# 03-Front_Panel_SFP_1.net
KiCad netlist of a schematic drawn in Altium Designer
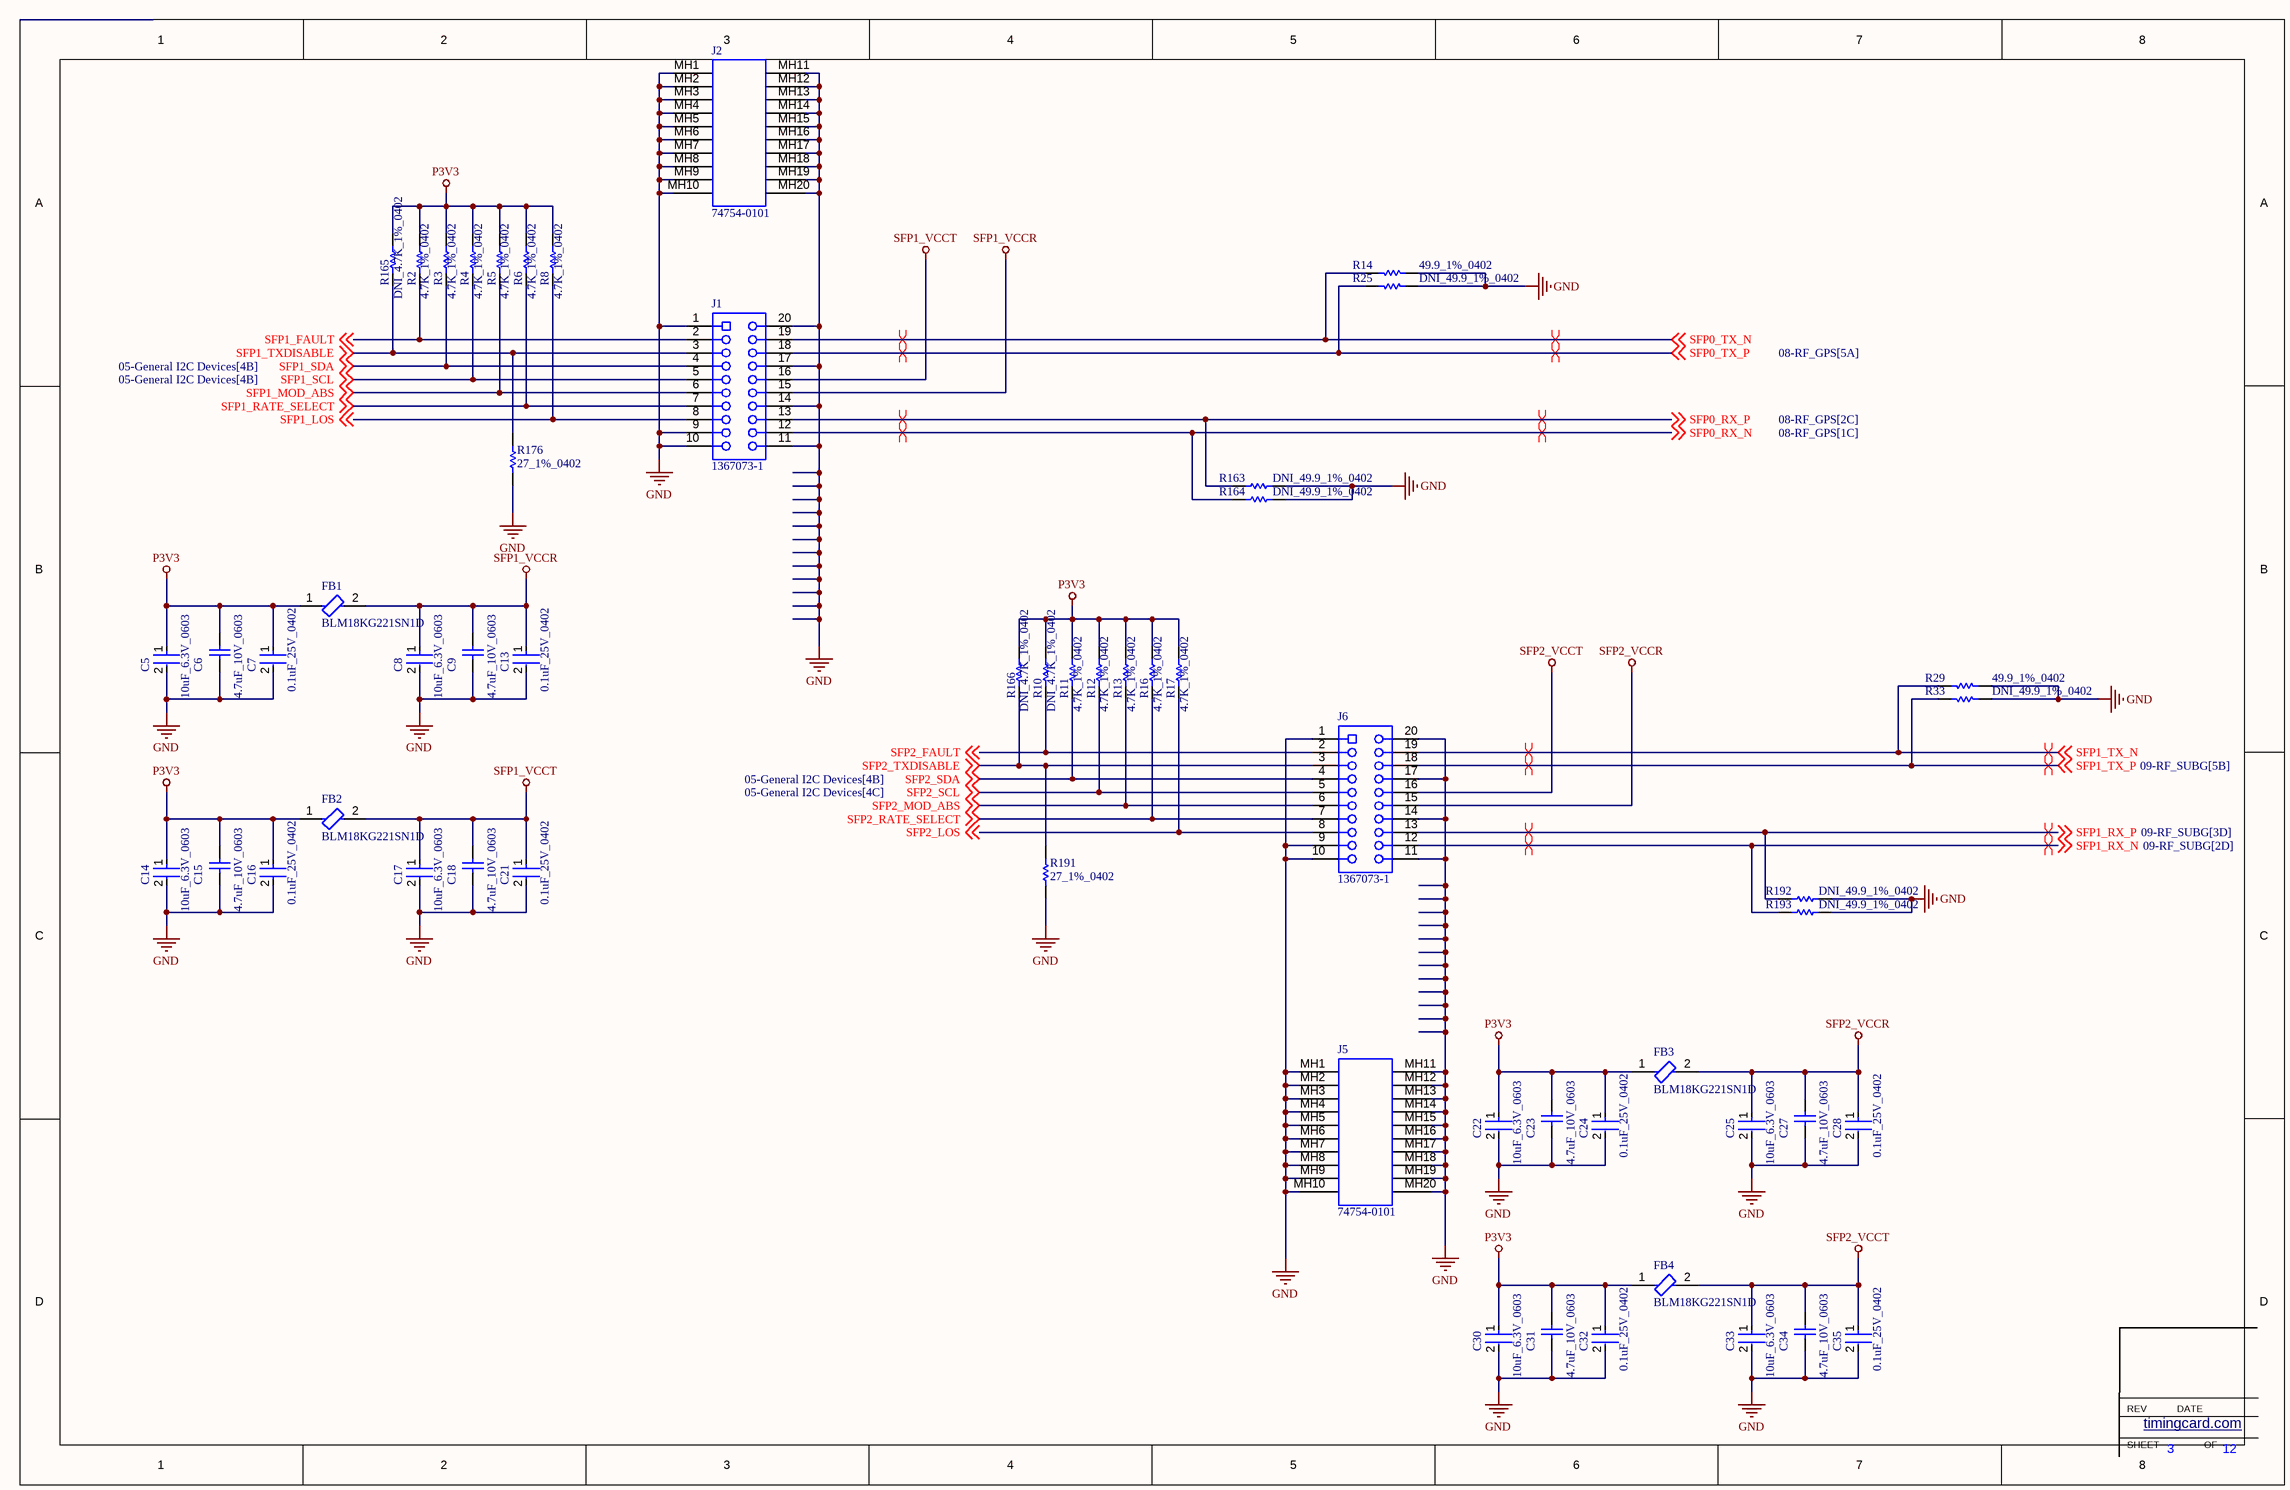
[diagram p0: 03-Front Panel SFP_1.SchDoc]

(export (version "E")
  (design (tool "Eeschema 10.0.6"))
  (components
    (comp (ref "C5")
      (value "10uF_6.3V_0603")
      (footprint "FP-C0603C106M9PACTU-MFG")
      (description "CAP CER 10UF 6.3V X5R 0603")
      (fields
        (field (name "MANUFACTURER PART NUMBER") "C0603C106M9PACTU")
        (field (name "MANUFACTURER") "Kemet")
      )
      (libsource (lib "Altium Content Vault") (part "b4654b650e69147ec39a6b967a45e02"))
    )
    (comp (ref "C6")
      (value "4.7uF_10V_0603")
      (footprint "CAPC1608X87X35NL15T15")
      (fields (field (name "PART NUMBER") "C0603C475K8PACTU") (field (name "MANUFACTURER") "Kemet"))
      (libsource (lib "Altium Content Vault") (part "CAP"))
    )
    (comp (ref "C7")
      (value "0.1uF_25V_0402")
      (footprint "FP-0402-L_1_0_1-W_0_5_0_1-IPC_C")
      (description "General Purpose Ceramic Capacitor, 0402, 100nF, 10%, X7R, 15%, 25V")
      (fields (field (name "VOLTAGE") "25V") (field (name "TOLERANCE") "10%"))
      (libsource (lib "Altium Content Vault") (part "b4654b650e69147ec39a6b967a45e02"))
    )
    (comp (ref "C8")
      (value "10uF_6.3V_0603")
      (footprint "FP-C0603C106M9PACTU-MFG")
      (description "CAP CER 10UF 6.3V X5R 0603")
      (fields
        (field (name "MANUFACTURER PART NUMBER") "C0603C106M9PACTU")
        (field (name "MANUFACTURER") "Kemet")
      )
      (libsource (lib "Altium Content Vault") (part "b4654b650e69147ec39a6b967a45e02"))
    )
    (comp (ref "C9")
      (value "4.7uF_10V_0603")
      (footprint "CAPC1608X87X35NL15T15")
      (fields (field (name "PART NUMBER") "C0603C475K8PACTU") (field (name "MANUFACTURER") "Kemet"))
      (libsource (lib "Altium Content Vault") (part "CAP"))
    )
    (comp (ref "C13")
      (value "0.1uF_25V_0402")
      (footprint "FP-0402-L_1_0_1-W_0_5_0_1-IPC_C")
      (description "General Purpose Ceramic Capacitor, 0402, 100nF, 10%, X7R, 15%, 25V")
      (fields (field (name "VOLTAGE") "25V") (field (name "TOLERANCE") "10%"))
      (libsource (lib "Altium Content Vault") (part "b4654b650e69147ec39a6b967a45e02"))
    )
    (comp (ref "C14")
      (value "10uF_6.3V_0603")
      (footprint "FP-C0603C106M9PACTU-MFG")
      (description "CAP CER 10UF 6.3V X5R 0603")
      (fields
        (field (name "MANUFACTURER PART NUMBER") "C0603C106M9PACTU")
        (field (name "MANUFACTURER") "Kemet")
      )
      (libsource (lib "Altium Content Vault") (part "b4654b650e69147ec39a6b967a45e02"))
    )
    (comp (ref "C15")
      (value "4.7uF_10V_0603")
      (footprint "CAPC1608X87X35NL15T15")
      (fields (field (name "PART NUMBER") "C0603C475K8PACTU") (field (name "MANUFACTURER") "Kemet"))
      (libsource (lib "Altium Content Vault") (part "CAP"))
    )
    (comp (ref "C16")
      (value "0.1uF_25V_0402")
      (footprint "FP-0402-L_1_0_1-W_0_5_0_1-IPC_C")
      (description "General Purpose Ceramic Capacitor, 0402, 100nF, 10%, X7R, 15%, 25V")
      (fields (field (name "VOLTAGE") "25V") (field (name "TOLERANCE") "10%"))
      (libsource (lib "Altium Content Vault") (part "b4654b650e69147ec39a6b967a45e02"))
    )
    (comp (ref "C17")
      (value "10uF_6.3V_0603")
      (footprint "FP-C0603C106M9PACTU-MFG")
      (description "CAP CER 10UF 6.3V X5R 0603")
      (fields
        (field (name "MANUFACTURER PART NUMBER") "C0603C106M9PACTU")
        (field (name "MANUFACTURER") "Kemet")
      )
      (libsource (lib "Altium Content Vault") (part "b4654b650e69147ec39a6b967a45e02"))
    )
    (comp (ref "C18")
      (value "4.7uF_10V_0603")
      (footprint "CAPC1608X87X35NL15T15")
      (fields (field (name "PART NUMBER") "C0603C475K8PACTU") (field (name "MANUFACTURER") "Kemet"))
      (libsource (lib "Altium Content Vault") (part "CAP"))
    )
    (comp (ref "C21")
      (value "0.1uF_25V_0402")
      (footprint "FP-0402-L_1_0_1-W_0_5_0_1-IPC_C")
      (description "General Purpose Ceramic Capacitor, 0402, 100nF, 10%, X7R, 15%, 25V")
      (fields (field (name "VOLTAGE") "25V") (field (name "TOLERANCE") "10%"))
      (libsource (lib "Altium Content Vault") (part "b4654b650e69147ec39a6b967a45e02"))
    )
    (comp (ref "C22")
      (value "10uF_6.3V_0603")
      (footprint "FP-C0603C106M9PACTU-MFG")
      (description "CAP CER 10UF 6.3V X5R 0603")
      (fields
        (field (name "MANUFACTURER PART NUMBER") "C0603C106M9PACTU")
        (field (name "MANUFACTURER") "Kemet")
      )
      (libsource (lib "Altium Content Vault") (part "b4654b650e69147ec39a6b967a45e02"))
    )
    (comp (ref "C23")
      (value "4.7uF_10V_0603")
      (footprint "CAPC1608X87X35NL15T15")
      (fields (field (name "PART NUMBER") "C0603C475K8PACTU") (field (name "MANUFACTURER") "Kemet"))
      (libsource (lib "Altium Content Vault") (part "CAP"))
    )
    (comp (ref "C24")
      (value "0.1uF_25V_0402")
      (footprint "FP-0402-L_1_0_1-W_0_5_0_1-IPC_C")
      (description "General Purpose Ceramic Capacitor, 0402, 100nF, 10%, X7R, 15%, 25V")
      (fields (field (name "VOLTAGE") "25V") (field (name "TOLERANCE") "10%"))
      (libsource (lib "Altium Content Vault") (part "b4654b650e69147ec39a6b967a45e02"))
    )
    (comp (ref "C25")
      (value "10uF_6.3V_0603")
      (footprint "FP-C0603C106M9PACTU-MFG")
      (description "CAP CER 10UF 6.3V X5R 0603")
      (fields
        (field (name "MANUFACTURER PART NUMBER") "C0603C106M9PACTU")
        (field (name "MANUFACTURER") "Kemet")
      )
      (libsource (lib "Altium Content Vault") (part "b4654b650e69147ec39a6b967a45e02"))
    )
    (comp (ref "C27")
      (value "4.7uF_10V_0603")
      (footprint "CAPC1608X87X35NL15T15")
      (fields (field (name "PART NUMBER") "C0603C475K8PACTU") (field (name "MANUFACTURER") "Kemet"))
      (libsource (lib "Altium Content Vault") (part "CAP"))
    )
    (comp (ref "C28")
      (value "0.1uF_25V_0402")
      (footprint "FP-0402-L_1_0_1-W_0_5_0_1-IPC_C")
      (description "General Purpose Ceramic Capacitor, 0402, 100nF, 10%, X7R, 15%, 25V")
      (fields (field (name "VOLTAGE") "25V") (field (name "TOLERANCE") "10%"))
      (libsource (lib "Altium Content Vault") (part "b4654b650e69147ec39a6b967a45e02"))
    )
    (comp (ref "C30")
      (value "10uF_6.3V_0603")
      (footprint "FP-C0603C106M9PACTU-MFG")
      (description "CAP CER 10UF 6.3V X5R 0603")
      (fields
        (field (name "MANUFACTURER PART NUMBER") "C0603C106M9PACTU")
        (field (name "MANUFACTURER") "Kemet")
      )
      (libsource (lib "Altium Content Vault") (part "b4654b650e69147ec39a6b967a45e02"))
    )
    (comp (ref "C31")
      (value "4.7uF_10V_0603")
      (footprint "CAPC1608X87X35NL15T15")
      (fields (field (name "PART NUMBER") "C0603C475K8PACTU") (field (name "MANUFACTURER") "Kemet"))
      (libsource (lib "Altium Content Vault") (part "CAP"))
    )
    (comp (ref "C32")
      (value "0.1uF_25V_0402")
      (footprint "FP-0402-L_1_0_1-W_0_5_0_1-IPC_C")
      (description "General Purpose Ceramic Capacitor, 0402, 100nF, 10%, X7R, 15%, 25V")
      (fields (field (name "VOLTAGE") "25V") (field (name "TOLERANCE") "10%"))
      (libsource (lib "Altium Content Vault") (part "b4654b650e69147ec39a6b967a45e02"))
    )
    (comp (ref "C33")
      (value "10uF_6.3V_0603")
      (footprint "FP-C0603C106M9PACTU-MFG")
      (description "CAP CER 10UF 6.3V X5R 0603")
      (fields
        (field (name "MANUFACTURER PART NUMBER") "C0603C106M9PACTU")
        (field (name "MANUFACTURER") "Kemet")
      )
      (libsource (lib "Altium Content Vault") (part "b4654b650e69147ec39a6b967a45e02"))
    )
    (comp (ref "C34")
      (value "4.7uF_10V_0603")
      (footprint "CAPC1608X87X35NL15T15")
      (fields (field (name "PART NUMBER") "C0603C475K8PACTU") (field (name "MANUFACTURER") "Kemet"))
      (libsource (lib "Altium Content Vault") (part "CAP"))
    )
    (comp (ref "C35")
      (value "0.1uF_25V_0402")
      (footprint "FP-0402-L_1_0_1-W_0_5_0_1-IPC_C")
      (description "General Purpose Ceramic Capacitor, 0402, 100nF, 10%, X7R, 15%, 25V")
      (fields (field (name "VOLTAGE") "25V") (field (name "TOLERANCE") "10%"))
      (libsource (lib "Altium Content Vault") (part "b4654b650e69147ec39a6b967a45e02"))
    )
    (comp (ref "FB1")
      (value "BLM18KG221SN1D")
      (footprint "FP-BLM18-0_15-t0_8-IPC_B")
      (description "Chip Ferrite Bead, 0603, 220Ω @ 100MHz, 0.05Ω, 25%, 2.2A")
      (fields (field (name "TOLERANCE") "25%"))
      (libsource (lib "Altium Content Vault") (part "5f30dd21d616792df468990f7003faa"))
    )
    (comp (ref "FB2")
      (value "BLM18KG221SN1D")
      (footprint "FP-BLM18-0_15-t0_8-IPC_B")
      (description "Chip Ferrite Bead, 0603, 220Ω @ 100MHz, 0.05Ω, 25%, 2.2A")
      (fields (field (name "TOLERANCE") "25%"))
      (libsource (lib "Altium Content Vault") (part "5f30dd21d616792df468990f7003faa"))
    )
    (comp (ref "FB3")
      (value "BLM18KG221SN1D")
      (footprint "FP-BLM18-0_15-t0_8-IPC_B")
      (description "Chip Ferrite Bead, 0603, 220Ω @ 100MHz, 0.05Ω, 25%, 2.2A")
      (fields (field (name "TOLERANCE") "25%"))
      (libsource (lib "Altium Content Vault") (part "5f30dd21d616792df468990f7003faa"))
    )
    (comp (ref "FB4")
      (value "BLM18KG221SN1D")
      (footprint "FP-BLM18-0_15-t0_8-IPC_B")
      (description "Chip Ferrite Bead, 0603, 220Ω @ 100MHz, 0.05Ω, 25%, 2.2A")
      (fields (field (name "TOLERANCE") "25%"))
      (libsource (lib "Altium Content Vault") (part "5f30dd21d616792df468990f7003faa"))
    )
    (comp (ref "J1")
      (value "1367073-1")
      (footprint "TECO-1367073-1_V")
      (fields (field (name "MANUFACTURER") "TE Connectivity"))
      (libsource (lib "Altium Content Vault") (part "CN-2P-F-R20_B"))
    )
    (comp (ref "J2")
      (value "74754-0101")
      (footprint "MOLX-74754-0101_V")
      (description "SFP+ Cage, Single Port, Height 10.85 mm, Tail Height 3.05 mm, -40 to 85 degC, RoHS, Tray")
      (libsource (lib "Altium Content Vault") (part "MOLX-74754-0101"))
    )
    (comp (ref "J5")
      (value "74754-0101")
      (footprint "MOLX-74754-0101_V")
      (description "SFP+ Cage, Single Port, Height 10.85 mm, Tail Height 3.05 mm, -40 to 85 degC, RoHS, Tray")
      (libsource (lib "Altium Content Vault") (part "MOLX-74754-0101"))
    )
    (comp (ref "J6")
      (value "1367073-1")
      (footprint "TECO-1367073-1_V")
      (fields (field (name "MANUFACTURER") "TE Connectivity"))
      (libsource (lib "Altium Content Vault") (part "CN-2P-F-R20_B"))
    )
    (comp (ref "R2")
      (value "4.7K_1%_0402")
      (footprint "RESC1005X40X25NL10T10")
      (fields (field (name "MANUFACTURER") "Bourns") (field (name "PART NUMBER") "CR0402-FX-4701GLF"))
      (libsource (lib "Altium Content Vault") (part "RES"))
    )
    (comp (ref "R3")
      (value "4.7K_1%_0402")
      (footprint "RESC1005X40X25NL10T10")
      (fields (field (name "MANUFACTURER") "Bourns") (field (name "PART NUMBER") "CR0402-FX-4701GLF"))
      (libsource (lib "Altium Content Vault") (part "RES"))
    )
    (comp (ref "R4")
      (value "4.7K_1%_0402")
      (footprint "RESC1005X40X25NL10T10")
      (fields (field (name "MANUFACTURER") "Bourns") (field (name "PART NUMBER") "CR0402-FX-4701GLF"))
      (libsource (lib "Altium Content Vault") (part "RES"))
    )
    (comp (ref "R5")
      (value "4.7K_1%_0402")
      (footprint "RESC1005X40X25NL10T10")
      (fields (field (name "MANUFACTURER") "Bourns") (field (name "PART NUMBER") "CR0402-FX-4701GLF"))
      (libsource (lib "Altium Content Vault") (part "RES"))
    )
    (comp (ref "R6")
      (value "4.7K_1%_0402")
      (footprint "RESC1005X40X25NL10T10")
      (fields (field (name "MANUFACTURER") "Bourns") (field (name "PART NUMBER") "CR0402-FX-4701GLF"))
      (libsource (lib "Altium Content Vault") (part "RES"))
    )
    (comp (ref "R8")
      (value "4.7K_1%_0402")
      (footprint "RESC1005X40X25NL10T10")
      (fields (field (name "MANUFACTURER") "Bourns") (field (name "PART NUMBER") "CR0402-FX-4701GLF"))
      (libsource (lib "Altium Content Vault") (part "RES"))
    )
    (comp (ref "R10")
      (value "DNI_4.7K_1%_0402")
      (footprint "RESC1005X40X25NL10T10")
      (fields (field (name "MANUFACTURER") "Bourns") (field (name "PART NUMBER") "CR0402-FX-4701GLF"))
      (libsource (lib "Altium Content Vault") (part "RES"))
    )
    (comp (ref "R11")
      (value "4.7K_1%_0402")
      (footprint "RESC1005X40X25NL10T10")
      (fields (field (name "MANUFACTURER") "Bourns") (field (name "PART NUMBER") "CR0402-FX-4701GLF"))
      (libsource (lib "Altium Content Vault") (part "RES"))
    )
    (comp (ref "R12")
      (value "4.7K_1%_0402")
      (footprint "RESC1005X40X25NL10T10")
      (fields (field (name "MANUFACTURER") "Bourns") (field (name "PART NUMBER") "CR0402-FX-4701GLF"))
      (libsource (lib "Altium Content Vault") (part "RES"))
    )
    (comp (ref "R13")
      (value "4.7K_1%_0402")
      (footprint "RESC1005X40X25NL10T10")
      (fields (field (name "MANUFACTURER") "Bourns") (field (name "PART NUMBER") "CR0402-FX-4701GLF"))
      (libsource (lib "Altium Content Vault") (part "RES"))
    )
    (comp (ref "R14")
      (value "49.9_1%_0402")
      (footprint "RESC1005X40X25NL10T10")
      (fields (field (name "PART NUMBER") "RK73H1ETTP49R9F") (field (name "MANUFACTURER") "KOA Speer"))
      (libsource (lib "Altium Content Vault") (part "RES"))
    )
    (comp (ref "R16")
      (value "4.7K_1%_0402")
      (footprint "RESC1005X40X25NL10T10")
      (fields (field (name "MANUFACTURER") "Bourns") (field (name "PART NUMBER") "CR0402-FX-4701GLF"))
      (libsource (lib "Altium Content Vault") (part "RES"))
    )
    (comp (ref "R17")
      (value "4.7K_1%_0402")
      (footprint "RESC1005X40X25NL10T10")
      (fields (field (name "MANUFACTURER") "Bourns") (field (name "PART NUMBER") "CR0402-FX-4701GLF"))
      (libsource (lib "Altium Content Vault") (part "RES"))
    )
    (comp (ref "R25")
      (value "DNI_49.9_1%_0402")
      (footprint "RESC1005X40X25NL10T10")
      (fields (field (name "PART NUMBER") "RK73H1ETTP49R9F") (field (name "MANUFACTURER") "KOA Speer"))
      (libsource (lib "Altium Content Vault") (part "RES"))
    )
    (comp (ref "R29")
      (value "49.9_1%_0402")
      (footprint "RESC1005X40X25NL10T10")
      (fields (field (name "PART NUMBER") "RK73H1ETTP49R9F") (field (name "MANUFACTURER") "KOA Speer"))
      (libsource (lib "Altium Content Vault") (part "RES"))
    )
    (comp (ref "R33")
      (value "DNI_49.9_1%_0402")
      (footprint "RESC1005X40X25NL10T10")
      (fields (field (name "PART NUMBER") "RK73H1ETTP49R9F") (field (name "MANUFACTURER") "KOA Speer"))
      (libsource (lib "Altium Content Vault") (part "RES"))
    )
    (comp (ref "R163")
      (value "DNI_49.9_1%_0402")
      (footprint "RESC1005X40X25NL10T10")
      (fields (field (name "PART NUMBER") "RK73H1ETTP49R9F") (field (name "MANUFACTURER") "KOA Speer"))
      (libsource (lib "Altium Content Vault") (part "RES"))
    )
    (comp (ref "R164")
      (value "DNI_49.9_1%_0402")
      (footprint "RESC1005X40X25NL10T10")
      (fields (field (name "PART NUMBER") "RK73H1ETTP49R9F") (field (name "MANUFACTURER") "KOA Speer"))
      (libsource (lib "Altium Content Vault") (part "RES"))
    )
    (comp (ref "R165")
      (value "DNI_4.7K_1%_0402")
      (footprint "RESC1005X40X25NL10T10")
      (fields (field (name "MANUFACTURER") "Bourns") (field (name "PART NUMBER") "CR0402-FX-4701GLF"))
      (libsource (lib "Altium Content Vault") (part "RES"))
    )
    (comp (ref "R166")
      (value "DNI_4.7K_1%_0402")
      (footprint "RESC1005X40X25NL10T10")
      (fields (field (name "MANUFACTURER") "Bourns") (field (name "PART NUMBER") "CR0402-FX-4701GLF"))
      (libsource (lib "Altium Content Vault") (part "RES"))
    )
    (comp (ref "R176")
      (value "27_1%_0402")
      (footprint "RESC1005X40X25NL05T05")
      (fields (field (name "PART NUMBER") "CRCW040227R0FKED") (field (name "MANUFACTURER") "Vishay Dale"))
      (libsource (lib "Altium Content Vault") (part "RES"))
    )
    (comp (ref "R191")
      (value "27_1%_0402")
      (footprint "RESC1005X40X25NL05T05")
      (fields (field (name "PART NUMBER") "CRCW040227R0FKED") (field (name "MANUFACTURER") "Vishay Dale"))
      (libsource (lib "Altium Content Vault") (part "RES"))
    )
    (comp (ref "R192")
      (value "DNI_49.9_1%_0402")
      (footprint "RESC1005X40X25NL10T10")
      (fields (field (name "PART NUMBER") "RK73H1ETTP49R9F") (field (name "MANUFACTURER") "KOA Speer"))
      (libsource (lib "Altium Content Vault") (part "RES"))
    )
    (comp (ref "R193")
      (value "DNI_49.9_1%_0402")
      (footprint "RESC1005X40X25NL10T10")
      (fields (field (name "PART NUMBER") "RK73H1ETTP49R9F") (field (name "MANUFACTURER") "KOA Speer"))
      (libsource (lib "Altium Content Vault") (part "RES"))
    )
  )
  (nets
    (net (code "1") (name "GND") (class "Default")
      (node (ref "C13") (pin "2") (pinfunction "2_2") (pintype "passive"))
      (node (ref "C14") (pin "2") (pinfunction "2_2") (pintype "passive"))
      (node (ref "C15") (pin "1") (pinfunction "1_1") (pintype "passive"))
      (node (ref "C16") (pin "2") (pinfunction "2_2") (pintype "passive"))
      (node (ref "C17") (pin "2") (pinfunction "2_2") (pintype "passive"))
      (node (ref "C18") (pin "1") (pinfunction "1_1") (pintype "passive"))
      (node (ref "C21") (pin "2") (pinfunction "2_2") (pintype "passive"))
      (node (ref "C22") (pin "2") (pinfunction "2_2") (pintype "passive"))
      (node (ref "C23") (pin "1") (pinfunction "1_1") (pintype "passive"))
      (node (ref "C24") (pin "2") (pinfunction "2_2") (pintype "passive"))
      (node (ref "C25") (pin "2") (pinfunction "2_2") (pintype "passive"))
      (node (ref "C27") (pin "1") (pinfunction "1_1") (pintype "passive"))
      (node (ref "C28") (pin "2") (pinfunction "2_2") (pintype "passive"))
      (node (ref "C30") (pin "2") (pinfunction "2_2") (pintype "passive"))
      (node (ref "C31") (pin "1") (pinfunction "1_1") (pintype "passive"))
      (node (ref "C32") (pin "2") (pinfunction "2_2") (pintype "passive"))
      (node (ref "C33") (pin "2") (pinfunction "2_2") (pintype "passive"))
      (node (ref "C34") (pin "1") (pinfunction "1_1") (pintype "passive"))
      (node (ref "C35") (pin "2") (pinfunction "2_2") (pintype "passive"))
      (node (ref "C5") (pin "2") (pinfunction "2_2") (pintype "passive"))
      (node (ref "C6") (pin "1") (pinfunction "1_1") (pintype "passive"))
      (node (ref "C7") (pin "2") (pinfunction "2_2") (pintype "passive"))
      (node (ref "C8") (pin "2") (pinfunction "2_2") (pintype "passive"))
      (node (ref "C9") (pin "1") (pinfunction "1_1") (pintype "passive"))
      (node (ref "J1") (pin "1") (pinfunction "1_1") (pintype "passive"))
      (node (ref "J1") (pin "10") (pinfunction "10_10") (pintype "passive"))
      (node (ref "J1") (pin "11") (pinfunction "11_11") (pintype "passive"))
      (node (ref "J1") (pin "14") (pinfunction "14_14") (pintype "passive"))
      (node (ref "J1") (pin "17") (pinfunction "17_17") (pintype "passive"))
      (node (ref "J1") (pin "20") (pinfunction "20_20") (pintype "passive"))
      (node (ref "J1") (pin "9") (pinfunction "9_9") (pintype "passive"))
      (node (ref "J2") (pin "MH1") (pinfunction "MH1_MH1") (pintype "passive"))
      (node (ref "J2") (pin "MH10") (pinfunction "MH10_MH10") (pintype "passive"))
      (node (ref "J2") (pin "MH11") (pinfunction "MH11_MH11") (pintype "passive"))
      (node (ref "J2") (pin "MH12") (pinfunction "MH12_MH12") (pintype "passive"))
      (node (ref "J2") (pin "MH13") (pinfunction "MH13_MH13") (pintype "passive"))
      (node (ref "J2") (pin "MH14") (pinfunction "MH14_MH14") (pintype "passive"))
      (node (ref "J2") (pin "MH15") (pinfunction "MH15_MH15") (pintype "passive"))
      (node (ref "J2") (pin "MH16") (pinfunction "MH16_MH16") (pintype "passive"))
      (node (ref "J2") (pin "MH17") (pinfunction "MH17_MH17") (pintype "passive"))
      (node (ref "J2") (pin "MH18") (pinfunction "MH18_MH18") (pintype "passive"))
      (node (ref "J2") (pin "MH19") (pinfunction "MH19_MH19") (pintype "passive"))
      (node (ref "J2") (pin "MH2") (pinfunction "MH2_MH2") (pintype "passive"))
      (node (ref "J2") (pin "MH20") (pinfunction "MH20_MH20") (pintype "passive"))
      (node (ref "J2") (pin "MH3") (pinfunction "MH3_MH3") (pintype "passive"))
      (node (ref "J2") (pin "MH4") (pinfunction "MH4_MH4") (pintype "passive"))
      (node (ref "J2") (pin "MH5") (pinfunction "MH5_MH5") (pintype "passive"))
      (node (ref "J2") (pin "MH6") (pinfunction "MH6_MH6") (pintype "passive"))
      (node (ref "J2") (pin "MH7") (pinfunction "MH7_MH7") (pintype "passive"))
      (node (ref "J2") (pin "MH8") (pinfunction "MH8_MH8") (pintype "passive"))
      (node (ref "J2") (pin "MH9") (pinfunction "MH9_MH9") (pintype "passive"))
      (node (ref "J5") (pin "MH1") (pinfunction "MH1_MH1") (pintype "passive"))
      (node (ref "J5") (pin "MH10") (pinfunction "MH10_MH10") (pintype "passive"))
      (node (ref "J5") (pin "MH11") (pinfunction "MH11_MH11") (pintype "passive"))
      (node (ref "J5") (pin "MH12") (pinfunction "MH12_MH12") (pintype "passive"))
      (node (ref "J5") (pin "MH13") (pinfunction "MH13_MH13") (pintype "passive"))
      (node (ref "J5") (pin "MH14") (pinfunction "MH14_MH14") (pintype "passive"))
      (node (ref "J5") (pin "MH15") (pinfunction "MH15_MH15") (pintype "passive"))
      (node (ref "J5") (pin "MH16") (pinfunction "MH16_MH16") (pintype "passive"))
      (node (ref "J5") (pin "MH17") (pinfunction "MH17_MH17") (pintype "passive"))
      (node (ref "J5") (pin "MH18") (pinfunction "MH18_MH18") (pintype "passive"))
      (node (ref "J5") (pin "MH19") (pinfunction "MH19_MH19") (pintype "passive"))
      (node (ref "J5") (pin "MH2") (pinfunction "MH2_MH2") (pintype "passive"))
      (node (ref "J5") (pin "MH20") (pinfunction "MH20_MH20") (pintype "passive"))
      (node (ref "J5") (pin "MH3") (pinfunction "MH3_MH3") (pintype "passive"))
      (node (ref "J5") (pin "MH4") (pinfunction "MH4_MH4") (pintype "passive"))
      (node (ref "J5") (pin "MH5") (pinfunction "MH5_MH5") (pintype "passive"))
      (node (ref "J5") (pin "MH6") (pinfunction "MH6_MH6") (pintype "passive"))
      (node (ref "J5") (pin "MH7") (pinfunction "MH7_MH7") (pintype "passive"))
      (node (ref "J5") (pin "MH8") (pinfunction "MH8_MH8") (pintype "passive"))
      (node (ref "J5") (pin "MH9") (pinfunction "MH9_MH9") (pintype "passive"))
      (node (ref "J6") (pin "1") (pinfunction "1_1") (pintype "passive"))
      (node (ref "J6") (pin "10") (pinfunction "10_10") (pintype "passive"))
      (node (ref "J6") (pin "11") (pinfunction "11_11") (pintype "passive"))
      (node (ref "J6") (pin "14") (pinfunction "14_14") (pintype "passive"))
      (node (ref "J6") (pin "17") (pinfunction "17_17") (pintype "passive"))
      (node (ref "J6") (pin "20") (pinfunction "20_20") (pintype "passive"))
      (node (ref "J6") (pin "9") (pinfunction "9_9") (pintype "passive"))
      (node (ref "R14") (pin "2") (pinfunction "2_2") (pintype "passive"))
      (node (ref "R163") (pin "2") (pinfunction "2_2") (pintype "passive"))
      (node (ref "R164") (pin "2") (pinfunction "2_2") (pintype "passive"))
      (node (ref "R176") (pin "1") (pinfunction "1_1") (pintype "passive"))
      (node (ref "R191") (pin "1") (pinfunction "1_1") (pintype "passive"))
      (node (ref "R192") (pin "2") (pinfunction "2_2") (pintype "passive"))
      (node (ref "R193") (pin "2") (pinfunction "2_2") (pintype "passive"))
      (node (ref "R25") (pin "2") (pinfunction "2_2") (pintype "passive"))
      (node (ref "R29") (pin "2") (pinfunction "2_2") (pintype "passive"))
      (node (ref "R33") (pin "2") (pinfunction "2_2") (pintype "passive"))
    )
    (net (code "2") (name "P3V3") (class "Default")
      (node (ref "C14") (pin "1") (pinfunction "1_1") (pintype "passive"))
      (node (ref "C15") (pin "2") (pinfunction "2_2") (pintype "passive"))
      (node (ref "C16") (pin "1") (pinfunction "1_1") (pintype "passive"))
      (node (ref "C22") (pin "1") (pinfunction "1_1") (pintype "passive"))
      (node (ref "C23") (pin "2") (pinfunction "2_2") (pintype "passive"))
      (node (ref "C24") (pin "1") (pinfunction "1_1") (pintype "passive"))
      (node (ref "C30") (pin "1") (pinfunction "1_1") (pintype "passive"))
      (node (ref "C31") (pin "2") (pinfunction "2_2") (pintype "passive"))
      (node (ref "C32") (pin "1") (pinfunction "1_1") (pintype "passive"))
      (node (ref "C5") (pin "1") (pinfunction "1_1") (pintype "passive"))
      (node (ref "C6") (pin "2") (pinfunction "2_2") (pintype "passive"))
      (node (ref "C7") (pin "1") (pinfunction "1_1") (pintype "passive"))
      (node (ref "FB1") (pin "1") (pinfunction "1_1") (pintype "passive"))
      (node (ref "FB2") (pin "1") (pinfunction "1_1") (pintype "passive"))
      (node (ref "FB3") (pin "1") (pinfunction "1_1") (pintype "passive"))
      (node (ref "FB4") (pin "1") (pinfunction "1_1") (pintype "passive"))
      (node (ref "R10") (pin "1") (pinfunction "1_1") (pintype "passive"))
      (node (ref "R11") (pin "1") (pinfunction "1_1") (pintype "passive"))
      (node (ref "R12") (pin "1") (pinfunction "1_1") (pintype "passive"))
      (node (ref "R13") (pin "1") (pinfunction "1_1") (pintype "passive"))
      (node (ref "R16") (pin "1") (pinfunction "1_1") (pintype "passive"))
      (node (ref "R165") (pin "1") (pinfunction "1_1") (pintype "passive"))
      (node (ref "R166") (pin "1") (pinfunction "1_1") (pintype "passive"))
      (node (ref "R17") (pin "1") (pinfunction "1_1") (pintype "passive"))
      (node (ref "R2") (pin "1") (pinfunction "1_1") (pintype "passive"))
      (node (ref "R3") (pin "1") (pinfunction "1_1") (pintype "passive"))
      (node (ref "R4") (pin "1") (pinfunction "1_1") (pintype "passive"))
      (node (ref "R5") (pin "1") (pinfunction "1_1") (pintype "passive"))
      (node (ref "R6") (pin "1") (pinfunction "1_1") (pintype "passive"))
      (node (ref "R8") (pin "1") (pinfunction "1_1") (pintype "passive"))
    )
    (net (code "3") (name "SFP0_RX_N") (class "Default")
      (node (ref "J1") (pin "12") (pinfunction "12_12") (pintype "passive"))
      (node (ref "R164") (pin "1") (pinfunction "1_1") (pintype "passive"))
    )
    (net (code "4") (name "SFP0_RX_P") (class "Default")
      (node (ref "J1") (pin "13") (pinfunction "13_13") (pintype "passive"))
      (node (ref "R163") (pin "1") (pinfunction "1_1") (pintype "passive"))
    )
    (net (code "5") (name "SFP0_TX_N") (class "Default")
      (node (ref "J1") (pin "19") (pinfunction "19_19") (pintype "passive"))
      (node (ref "R14") (pin "1") (pinfunction "1_1") (pintype "passive"))
    )
    (net (code "6") (name "SFP0_TX_P") (class "Default")
      (node (ref "J1") (pin "18") (pinfunction "18_18") (pintype "passive"))
      (node (ref "R25") (pin "1") (pinfunction "1_1") (pintype "passive"))
    )
    (net (code "7") (name "SFP1_FAULT") (class "Default")
      (node (ref "J1") (pin "2") (pinfunction "2_2") (pintype "passive"))
      (node (ref "R2") (pin "2") (pinfunction "2_2") (pintype "passive"))
    )
    (net (code "8") (name "SFP1_LOS") (class "Default")
      (node (ref "J1") (pin "8") (pinfunction "8_8") (pintype "passive"))
      (node (ref "R8") (pin "2") (pinfunction "2_2") (pintype "passive"))
    )
    (net (code "9") (name "SFP1_MOD_ABS") (class "Default")
      (node (ref "J1") (pin "6") (pinfunction "6_6") (pintype "passive"))
      (node (ref "R5") (pin "2") (pinfunction "2_2") (pintype "passive"))
    )
    (net (code "10") (name "SFP1_RATE_SELECT") (class "Default")
      (node (ref "J1") (pin "7") (pinfunction "7_7") (pintype "passive"))
      (node (ref "R6") (pin "2") (pinfunction "2_2") (pintype "passive"))
    )
    (net (code "11") (name "SFP1_RX_N") (class "Default")
      (node (ref "J6") (pin "12") (pinfunction "12_12") (pintype "passive"))
      (node (ref "R193") (pin "1") (pinfunction "1_1") (pintype "passive"))
    )
    (net (code "12") (name "SFP1_RX_P") (class "Default")
      (node (ref "J6") (pin "13") (pinfunction "13_13") (pintype "passive"))
      (node (ref "R192") (pin "1") (pinfunction "1_1") (pintype "passive"))
    )
    (net (code "13") (name "SFP1_SCL") (class "Default")
      (node (ref "J1") (pin "5") (pinfunction "5_5") (pintype "passive"))
      (node (ref "R4") (pin "2") (pinfunction "2_2") (pintype "passive"))
    )
    (net (code "14") (name "SFP1_SDA") (class "Default")
      (node (ref "J1") (pin "4") (pinfunction "4_4") (pintype "passive"))
      (node (ref "R3") (pin "2") (pinfunction "2_2") (pintype "passive"))
    )
    (net (code "15") (name "SFP1_TXDISABLE") (class "Default")
      (node (ref "J1") (pin "3") (pinfunction "3_3") (pintype "passive"))
      (node (ref "R165") (pin "2") (pinfunction "2_2") (pintype "passive"))
      (node (ref "R176") (pin "2") (pinfunction "2_2") (pintype "passive"))
    )
    (net (code "16") (name "SFP1_TX_N") (class "Default")
      (node (ref "J6") (pin "19") (pinfunction "19_19") (pintype "passive"))
      (node (ref "R29") (pin "1") (pinfunction "1_1") (pintype "passive"))
    )
    (net (code "17") (name "SFP1_TX_P") (class "Default")
      (node (ref "J6") (pin "18") (pinfunction "18_18") (pintype "passive"))
      (node (ref "R33") (pin "1") (pinfunction "1_1") (pintype "passive"))
    )
    (net (code "18") (name "SFP1_VCCR") (class "Default")
      (node (ref "C13") (pin "1") (pinfunction "1_1") (pintype "passive"))
      (node (ref "C8") (pin "1") (pinfunction "1_1") (pintype "passive"))
      (node (ref "C9") (pin "2") (pinfunction "2_2") (pintype "passive"))
      (node (ref "FB1") (pin "2") (pinfunction "2_2") (pintype "passive"))
      (node (ref "J1") (pin "15") (pinfunction "15_15") (pintype "passive"))
    )
    (net (code "19") (name "SFP1_VCCT") (class "Default")
      (node (ref "C17") (pin "1") (pinfunction "1_1") (pintype "passive"))
      (node (ref "C18") (pin "2") (pinfunction "2_2") (pintype "passive"))
      (node (ref "C21") (pin "1") (pinfunction "1_1") (pintype "passive"))
      (node (ref "FB2") (pin "2") (pinfunction "2_2") (pintype "passive"))
      (node (ref "J1") (pin "16") (pinfunction "16_16") (pintype "passive"))
    )
    (net (code "20") (name "SFP2_FAULT") (class "Default")
      (node (ref "J6") (pin "2") (pinfunction "2_2") (pintype "passive"))
      (node (ref "R10") (pin "2") (pinfunction "2_2") (pintype "passive"))
    )
    (net (code "21") (name "SFP2_LOS") (class "Default")
      (node (ref "J6") (pin "8") (pinfunction "8_8") (pintype "passive"))
      (node (ref "R17") (pin "2") (pinfunction "2_2") (pintype "passive"))
    )
    (net (code "22") (name "SFP2_MOD_ABS") (class "Default")
      (node (ref "J6") (pin "6") (pinfunction "6_6") (pintype "passive"))
      (node (ref "R13") (pin "2") (pinfunction "2_2") (pintype "passive"))
    )
    (net (code "23") (name "SFP2_RATE_SELECT") (class "Default")
      (node (ref "J6") (pin "7") (pinfunction "7_7") (pintype "passive"))
      (node (ref "R16") (pin "2") (pinfunction "2_2") (pintype "passive"))
    )
    (net (code "24") (name "SFP2_SCL") (class "Default")
      (node (ref "J6") (pin "5") (pinfunction "5_5") (pintype "passive"))
      (node (ref "R12") (pin "2") (pinfunction "2_2") (pintype "passive"))
    )
    (net (code "25") (name "SFP2_SDA") (class "Default")
      (node (ref "J6") (pin "4") (pinfunction "4_4") (pintype "passive"))
      (node (ref "R11") (pin "2") (pinfunction "2_2") (pintype "passive"))
    )
    (net (code "26") (name "SFP2_TXDISABLE") (class "Default")
      (node (ref "J6") (pin "3") (pinfunction "3_3") (pintype "passive"))
      (node (ref "R166") (pin "2") (pinfunction "2_2") (pintype "passive"))
      (node (ref "R191") (pin "2") (pinfunction "2_2") (pintype "passive"))
    )
    (net (code "27") (name "SFP2_VCCR") (class "Default")
      (node (ref "C25") (pin "1") (pinfunction "1_1") (pintype "passive"))
      (node (ref "C27") (pin "2") (pinfunction "2_2") (pintype "passive"))
      (node (ref "C28") (pin "1") (pinfunction "1_1") (pintype "passive"))
      (node (ref "FB3") (pin "2") (pinfunction "2_2") (pintype "passive"))
      (node (ref "J6") (pin "15") (pinfunction "15_15") (pintype "passive"))
    )
    (net (code "28") (name "SFP2_VCCT") (class "Default")
      (node (ref "C33") (pin "1") (pinfunction "1_1") (pintype "passive"))
      (node (ref "C34") (pin "2") (pinfunction "2_2") (pintype "passive"))
      (node (ref "C35") (pin "1") (pinfunction "1_1") (pintype "passive"))
      (node (ref "FB4") (pin "2") (pinfunction "2_2") (pintype "passive"))
      (node (ref "J6") (pin "16") (pinfunction "16_16") (pintype "passive"))
    )
  )
)
